# G1-6.net
KiCad netlist of a schematic drawn in EAGLE
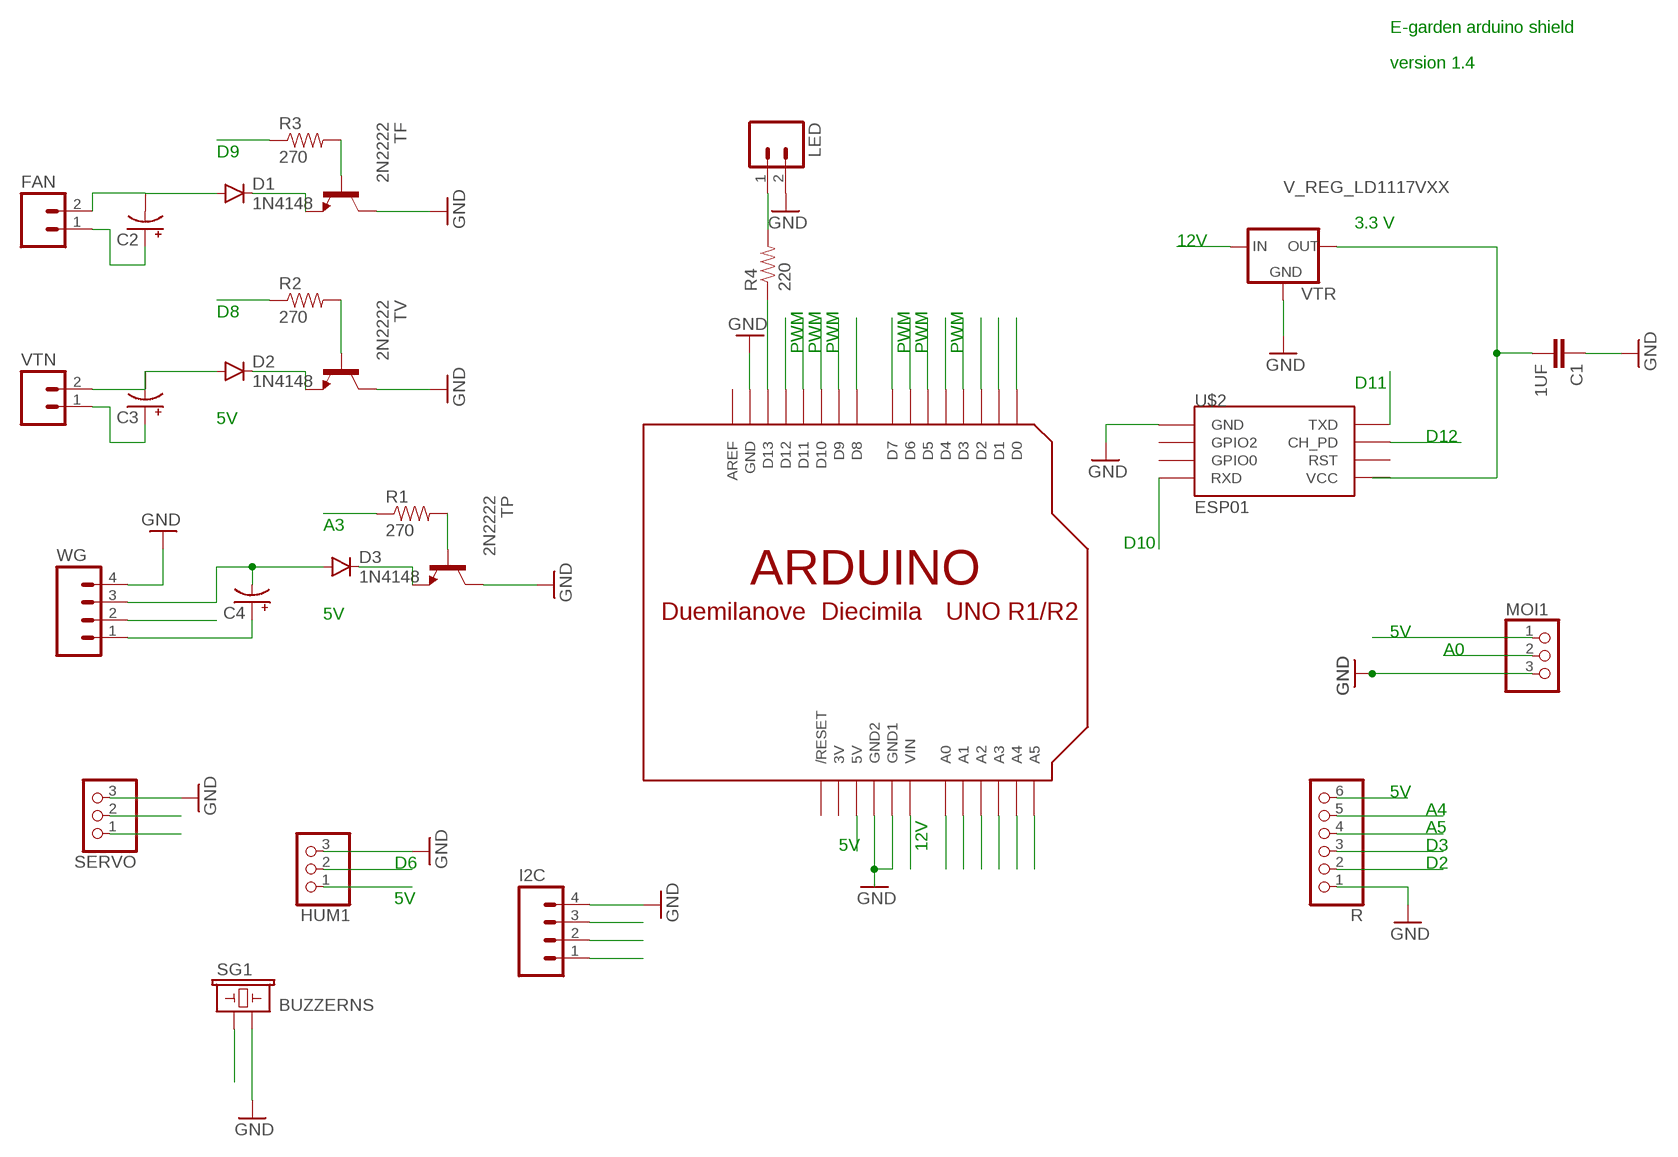
[diagram p0: schematic, sheet 1]

(export (version "E")
  (design (tool "Eeschema 10.0.6"))
  (components
    (comp (ref "C1")
      (value "1UF")
      (footprint "eagle-import:CAP-PTH-SMALL-KIT")
      (libsource (lib "eagle-import") (part "CAPKIT"))
    )
    (comp (ref "C2")
      (value "CAP_POLPTH2")
      (footprint "eagle-import:CPOL-RADIAL-10UF-25V")
      (libsource (lib "eagle-import") (part "CAP_POLPTH2"))
    )
    (comp (ref "C3")
      (value "CAP_POLPTH2")
      (footprint "eagle-import:CPOL-RADIAL-10UF-25V")
      (libsource (lib "eagle-import") (part "CAP_POLPTH2"))
    )
    (comp (ref "C4")
      (value "CAP_POLPTH2")
      (footprint "eagle-import:CPOL-RADIAL-10UF-25V")
      (libsource (lib "eagle-import") (part "CAP_POLPTH2"))
    )
    (comp (ref "D1")
      (value "1N4148")
      (footprint "eagle-import:DIODE-1N4148")
      (libsource (lib "eagle-import") (part "DIODE1N4148"))
    )
    (comp (ref "D2")
      (value "1N4148")
      (footprint "eagle-import:DIODE-1N4148")
      (libsource (lib "eagle-import") (part "DIODE1N4148"))
    )
    (comp (ref "D3")
      (value "1N4148")
      (footprint "eagle-import:DIODE-1N4148")
      (libsource (lib "eagle-import") (part "DIODE1N4148"))
    )
    (comp (ref "FAN")
      (value "M02PTH")
      (footprint "eagle-import:1X02")
      (libsource (lib "eagle-import") (part "M02PTH"))
    )
    (comp (ref "HUM1")
      (value "PINHD-1X3CB")
      (footprint "eagle-import:1X03-CLEANBIG")
      (libsource (lib "eagle-import") (part "PINHD-1X3CB"))
    )
    (comp (ref "I2C")
      (value "M04NO_SILK_ALL_ROUND")
      (footprint "eagle-import:1X04_NO_SILK_ALL_ROUND")
      (libsource (lib "eagle-import") (part "M04NO_SILK_ALL_ROUND"))
    )
    (comp (ref "LED")
      (value "M02PTH")
      (footprint "eagle-import:1X02")
      (libsource (lib "eagle-import") (part "M02PTH"))
    )
    (comp (ref "MOI1")
      (value "PINHD-1X3CB")
      (footprint "eagle-import:1X03-CLEANBIG")
      (libsource (lib "eagle-import") (part "PINHD-1X3CB"))
    )
    (comp (ref "R")
      (value "PINHD-1X6CB")
      (footprint "eagle-import:1X06-CLEANBIG")
      (libsource (lib "eagle-import") (part "PINHD-1X6CB"))
    )
    (comp (ref "R1")
      (value "270")
      (footprint "eagle-import:AXIAL-0.4")
      (libsource (lib "eagle-import") (part "RESISTORPTH-1/4W"))
    )
    (comp (ref "R2")
      (value "270")
      (footprint "eagle-import:AXIAL-0.4")
      (libsource (lib "eagle-import") (part "RESISTORPTH-1/4W"))
    )
    (comp (ref "R3")
      (value "270")
      (footprint "eagle-import:AXIAL-0.4")
      (libsource (lib "eagle-import") (part "RESISTORPTH-1/4W"))
    )
    (comp (ref "R4")
      (value "220")
      (footprint "eagle-import:AXIAL-0.4")
      (libsource (lib "eagle-import") (part "RESISTORPTH-1/4W"))
    )
    (comp (ref "SERVO")
      (value "PINHD-1X3CB")
      (footprint "eagle-import:1X03-CLEANBIG")
      (libsource (lib "eagle-import") (part "PINHD-1X3CB"))
    )
    (comp (ref "SG1")
      (value "BUZZERNS")
      (footprint "eagle-import:BUZZER-12MM-NS")
      (libsource (lib "eagle-import") (part "BUZZERNS"))
    )
    (comp (ref "TF")
      (value "2N2222")
      (footprint "eagle-import:TO92-EBC-OVAL")
      (libsource (lib "eagle-import") (part "2N2222"))
    )
    (comp (ref "TP")
      (value "2N2222")
      (footprint "eagle-import:TO92-EBC-OVAL")
      (libsource (lib "eagle-import") (part "2N2222"))
    )
    (comp (ref "TV")
      (value "2N2222")
      (footprint "eagle-import:TO92-EBC-OVAL")
      (libsource (lib "eagle-import") (part "2N2222"))
    )
    (comp (ref "U$1")
      (value "ARDUINO-BPLACE")
      (footprint "eagle-import:ARDUINO-BPLACE")
      (libsource (lib "eagle-import") (part "ARDUINO-BPLACE"))
    )
    (comp (ref "U$2")
      (value "ESP01")
      (footprint "eagle-import:ESP01")
      (libsource (lib "eagle-import") (part "ESP01"))
    )
    (comp (ref "VTN")
      (value "M02PTH")
      (footprint "eagle-import:1X02")
      (libsource (lib "eagle-import") (part "M02PTH"))
    )
    (comp (ref "VTR")
      (value "V_REG_LD1117VXX")
      (footprint "eagle-import:78XXL")
      (libsource (lib "eagle-import") (part "V_REG_LD1117VXX"))
    )
    (comp (ref "WG")
      (value "M04NO_SILK_ALL_ROUND")
      (footprint "eagle-import:1X04_NO_SILK_ALL_ROUND")
      (libsource (lib "eagle-import") (part "M04NO_SILK_ALL_ROUND"))
    )
  )
  (nets
    (net (code "1") (name "/3V") (class "Default")
      (node (ref "U$1") (pin "3V") (pinfunction "3V_3V") (pintype "power_in"))
    )
    (net (code "2") (name "/A0") (class "Default")
      (node (ref "MOI1") (pin "2") (pinfunction "2_2") (pintype "passive"))
      (node (ref "U$1") (pin "A0") (pinfunction "A0_A0") (pintype "bidirectional"))
    )
    (net (code "3") (name "/A1") (class "Default")
      (node (ref "U$1") (pin "A1") (pinfunction "A1_A1") (pintype "bidirectional"))
      (node (ref "WG") (pin "2") (pinfunction "2_2") (pintype "passive"))
    )
    (net (code "4") (name "/A2") (class "Default")
      (node (ref "R") (pin "4") (pinfunction "4_4") (pintype "passive"))
      (node (ref "U$1") (pin "A2") (pinfunction "A2_A2") (pintype "bidirectional"))
    )
    (net (code "5") (name "/A3") (class "Default")
      (node (ref "R") (pin "5") (pinfunction "5_5") (pintype "passive"))
      (node (ref "U$1") (pin "A3") (pinfunction "A3_A3") (pintype "bidirectional"))
    )
    (net (code "6") (name "/A4") (class "Default")
      (node (ref "I2C") (pin "3") (pinfunction "3_3") (pintype "passive"))
      (node (ref "U$1") (pin "A4") (pinfunction "A4_A4") (pintype "bidirectional"))
    )
    (net (code "7") (name "/A5") (class "Default")
      (node (ref "I2C") (pin "2") (pinfunction "2_2") (pintype "passive"))
      (node (ref "U$1") (pin "A5") (pinfunction "A5_A5") (pintype "bidirectional"))
    )
    (net (code "8") (name "/D2") (class "Default")
      (node (ref "R") (pin "3") (pinfunction "3_3") (pintype "passive"))
      (node (ref "U$1") (pin "D2") (pinfunction "D2_D2") (pintype "bidirectional"))
    )
    (net (code "9") (name "/D3") (class "Default")
      (node (ref "R") (pin "2") (pinfunction "2_2") (pintype "passive"))
      (node (ref "U$1") (pin "D3") (pinfunction "D3_D3") (pintype "bidirectional"))
    )
    (net (code "10") (name "/D4") (class "Default")
      (node (ref "SERVO") (pin "2") (pinfunction "2_2") (pintype "passive"))
      (node (ref "U$1") (pin "D4") (pinfunction "D4_D4") (pintype "bidirectional"))
    )
    (net (code "11") (name "/D5") (class "Default")
      (node (ref "SG1") (pin "+") (pinfunction "1_+") (pintype "passive"))
      (node (ref "U$1") (pin "D5") (pinfunction "D5_D5") (pintype "bidirectional"))
    )
    (net (code "12") (name "/D6") (class "Default")
      (node (ref "HUM1") (pin "2") (pinfunction "2_2") (pintype "passive"))
      (node (ref "U$1") (pin "D6") (pinfunction "D6_D6") (pintype "bidirectional"))
    )
    (net (code "13") (name "/D7") (class "Default")
      (node (ref "R1") (pin "P$1") (pinfunction "1_P$1") (pintype "passive"))
      (node (ref "U$1") (pin "D7") (pinfunction "D7_D7") (pintype "bidirectional"))
    )
    (net (code "14") (name "/D8") (class "Default")
      (node (ref "R2") (pin "P$1") (pinfunction "1_P$1") (pintype "passive"))
      (node (ref "U$1") (pin "D8") (pinfunction "D8_D8") (pintype "bidirectional"))
    )
    (net (code "15") (name "/D9") (class "Default")
      (node (ref "R3") (pin "P$1") (pinfunction "1_P$1") (pintype "passive"))
      (node (ref "U$1") (pin "D9") (pinfunction "D9_D9") (pintype "bidirectional"))
    )
    (net (code "16") (name "/D10") (class "Default")
      (node (ref "U$1") (pin "D10") (pinfunction "D10_D10") (pintype "bidirectional"))
      (node (ref "U$2") (pin "RX") (pinfunction "RXD_RX") (pintype "bidirectional"))
    )
    (net (code "17") (name "/D11") (class "Default")
      (node (ref "U$1") (pin "D11") (pinfunction "D11_D11") (pintype "bidirectional"))
      (node (ref "U$2") (pin "TX") (pinfunction "TXD_TX") (pintype "bidirectional"))
    )
    (net (code "18") (name "/D12") (class "Default")
      (node (ref "U$1") (pin "D12") (pinfunction "D12_D12") (pintype "bidirectional"))
      (node (ref "U$2") (pin "CH_PD") (pinfunction "CH_PD_CH_PD") (pintype "bidirectional"))
    )
    (net (code "19") (name "/V5") (class "Default")
      (node (ref "C2") (pin "1") (pinfunction "+_1") (pintype "passive"))
      (node (ref "C3") (pin "1") (pinfunction "+_1") (pintype "passive"))
      (node (ref "C4") (pin "1") (pinfunction "+_1") (pintype "passive"))
      (node (ref "FAN") (pin "1") (pinfunction "1_1") (pintype "passive"))
      (node (ref "HUM1") (pin "1") (pinfunction "1_1") (pintype "passive"))
      (node (ref "I2C") (pin "1") (pinfunction "1_1") (pintype "passive"))
      (node (ref "MOI1") (pin "1") (pinfunction "1_1") (pintype "passive"))
      (node (ref "R") (pin "6") (pinfunction "6_6") (pintype "passive"))
      (node (ref "SERVO") (pin "1") (pinfunction "1_1") (pintype "passive"))
      (node (ref "U$1") (pin "5V") (pinfunction "5V_5V") (pintype "power_in"))
      (node (ref "VTN") (pin "1") (pinfunction "1_1") (pintype "passive"))
      (node (ref "WG") (pin "1") (pinfunction "1_1") (pintype "passive"))
    )
    (net (code "20") (name "/V12") (class "Default")
      (node (ref "U$1") (pin "VIN") (pinfunction "VIN_VIN") (pintype "power_in"))
      (node (ref "VTR") (pin "OUT") (pinfunction "IN_OUT") (pintype "input"))
    )
    (net (code "21") (name "GND") (class "Default")
      (node (ref "C1") (pin "1") (pinfunction "1_1") (pintype "passive"))
      (node (ref "HUM1") (pin "3") (pinfunction "3_3") (pintype "passive"))
      (node (ref "I2C") (pin "4") (pinfunction "4_4") (pintype "passive"))
      (node (ref "LED") (pin "2") (pinfunction "2_2") (pintype "passive"))
      (node (ref "MOI1") (pin "3") (pinfunction "3_3") (pintype "passive"))
      (node (ref "R") (pin "1") (pinfunction "1_1") (pintype "passive"))
      (node (ref "SERVO") (pin "3") (pinfunction "3_3") (pintype "passive"))
      (node (ref "SG1") (pin "-") (pinfunction "2_-") (pintype "passive"))
      (node (ref "TF") (pin "C") (pinfunction "C_C") (pintype "passive"))
      (node (ref "TP") (pin "C") (pinfunction "C_C") (pintype "passive"))
      (node (ref "TV") (pin "C") (pinfunction "C_C") (pintype "passive"))
      (node (ref "U$1") (pin "GND") (pinfunction "GND_GND") (pintype "power_in"))
      (node (ref "U$1") (pin "GND1") (pinfunction "GND1_GND1") (pintype "power_in"))
      (node (ref "U$1") (pin "GND2") (pinfunction "GND2_GND2") (pintype "power_in"))
      (node (ref "U$2") (pin "GND") (pinfunction "GND_GND") (pintype "bidirectional"))
      (node (ref "VTR") (pin "IN") (pinfunction "GND_IN") (pintype "input"))
      (node (ref "WG") (pin "4") (pinfunction "4_4") (pintype "passive"))
    )
    (net (code "22") (name "Net-(C2--)") (class "Default")
      (node (ref "C2") (pin "2") (pinfunction "-_2") (pintype "passive"))
      (node (ref "D1") (pin "A") (pinfunction "A_A") (pintype "passive"))
      (node (ref "FAN") (pin "2") (pinfunction "2_2") (pintype "passive"))
    )
    (net (code "23") (name "Net-(C3--)") (class "Default")
      (node (ref "C3") (pin "2") (pinfunction "-_2") (pintype "passive"))
      (node (ref "D2") (pin "A") (pinfunction "A_A") (pintype "passive"))
      (node (ref "VTN") (pin "2") (pinfunction "2_2") (pintype "passive"))
    )
    (net (code "24") (name "Net-(C4--)") (class "Default")
      (node (ref "C4") (pin "2") (pinfunction "-_2") (pintype "passive"))
      (node (ref "D3") (pin "A") (pinfunction "A_A") (pintype "passive"))
      (node (ref "WG") (pin "3") (pinfunction "3_3") (pintype "passive"))
    )
    (net (code "25") (name "Net-(D1-PadC)") (class "Default")
      (node (ref "D1") (pin "C") (pinfunction "C_C") (pintype "passive"))
      (node (ref "TF") (pin "E") (pinfunction "E_E") (pintype "passive"))
    )
    (net (code "26") (name "Net-(D2-PadC)") (class "Default")
      (node (ref "D2") (pin "C") (pinfunction "C_C") (pintype "passive"))
      (node (ref "TV") (pin "E") (pinfunction "E_E") (pintype "passive"))
    )
    (net (code "27") (name "Net-(D3-PadC)") (class "Default")
      (node (ref "D3") (pin "C") (pinfunction "C_C") (pintype "passive"))
      (node (ref "TP") (pin "E") (pinfunction "E_E") (pintype "passive"))
    )
    (net (code "28") (name "Net-(R1-2)") (class "Default")
      (node (ref "R1") (pin "P$2") (pinfunction "2_P$2") (pintype "passive"))
      (node (ref "TP") (pin "B") (pinfunction "B_B") (pintype "passive"))
    )
    (net (code "29") (name "Net-(R2-2)") (class "Default")
      (node (ref "R2") (pin "P$2") (pinfunction "2_P$2") (pintype "passive"))
      (node (ref "TV") (pin "B") (pinfunction "B_B") (pintype "passive"))
    )
    (net (code "30") (name "Net-(R3-2)") (class "Default")
      (node (ref "R3") (pin "P$2") (pinfunction "2_P$2") (pintype "passive"))
      (node (ref "TF") (pin "B") (pinfunction "B_B") (pintype "passive"))
    )
    (net (code "31") (name "Net-(R4-1)") (class "Default")
      (node (ref "R4") (pin "P$1") (pinfunction "1_P$1") (pintype "passive"))
      (node (ref "U$1") (pin "D13") (pinfunction "D13_D13") (pintype "bidirectional"))
    )
    (net (code "32") (name "Net-(R4-2)") (class "Default")
      (node (ref "LED") (pin "1") (pinfunction "1_1") (pintype "passive"))
      (node (ref "R4") (pin "P$2") (pinfunction "2_P$2") (pintype "passive"))
    )
    (net (code "33") (name "Net-(VTR-OUT)") (class "Default")
      (node (ref "C1") (pin "2") (pinfunction "2_2") (pintype "passive"))
      (node (ref "U$2") (pin "VCC") (pinfunction "VCC_VCC") (pintype "bidirectional"))
      (node (ref "VTR") (pin "GND") (pinfunction "OUT_GND") (pintype "passive"))
    )
    (net (code "34") (name "unconnected-(U$1-PadAREF)") (class "Default")
      (node (ref "U$1") (pin "AREF") (pinfunction "AREF_AREF") (pintype "bidirectional"))
    )
    (net (code "35") (name "unconnected-(U$1-PadD0)") (class "Default")
      (node (ref "U$1") (pin "D0") (pinfunction "D0_D0") (pintype "bidirectional"))
    )
    (net (code "36") (name "unconnected-(U$1-PadD1)") (class "Default")
      (node (ref "U$1") (pin "D1") (pinfunction "D1_D1") (pintype "bidirectional"))
    )
    (net (code "37") (name "unconnected-(U$1-{slash}RESET-PadRESET)") (class "Default")
      (node (ref "U$1") (pin "RESET") (pinfunction "/RESET_RESET") (pintype "bidirectional"))
    )
    (net (code "38") (name "unconnected-(U$2-PadGPIO0)") (class "Default")
      (node (ref "U$2") (pin "GPIO0") (pinfunction "GPIO0_GPIO0") (pintype "bidirectional"))
    )
    (net (code "39") (name "unconnected-(U$2-PadGPIO2)") (class "Default")
      (node (ref "U$2") (pin "GPIO2") (pinfunction "GPIO2_GPIO2") (pintype "bidirectional"))
    )
    (net (code "40") (name "unconnected-(U$2-PadRST)") (class "Default")
      (node (ref "U$2") (pin "RST") (pinfunction "RST_RST") (pintype "bidirectional"))
    )
  )
)
